# STM32_CANbus_V01.net
KiCad netlist of a schematic drawn in EAGLE
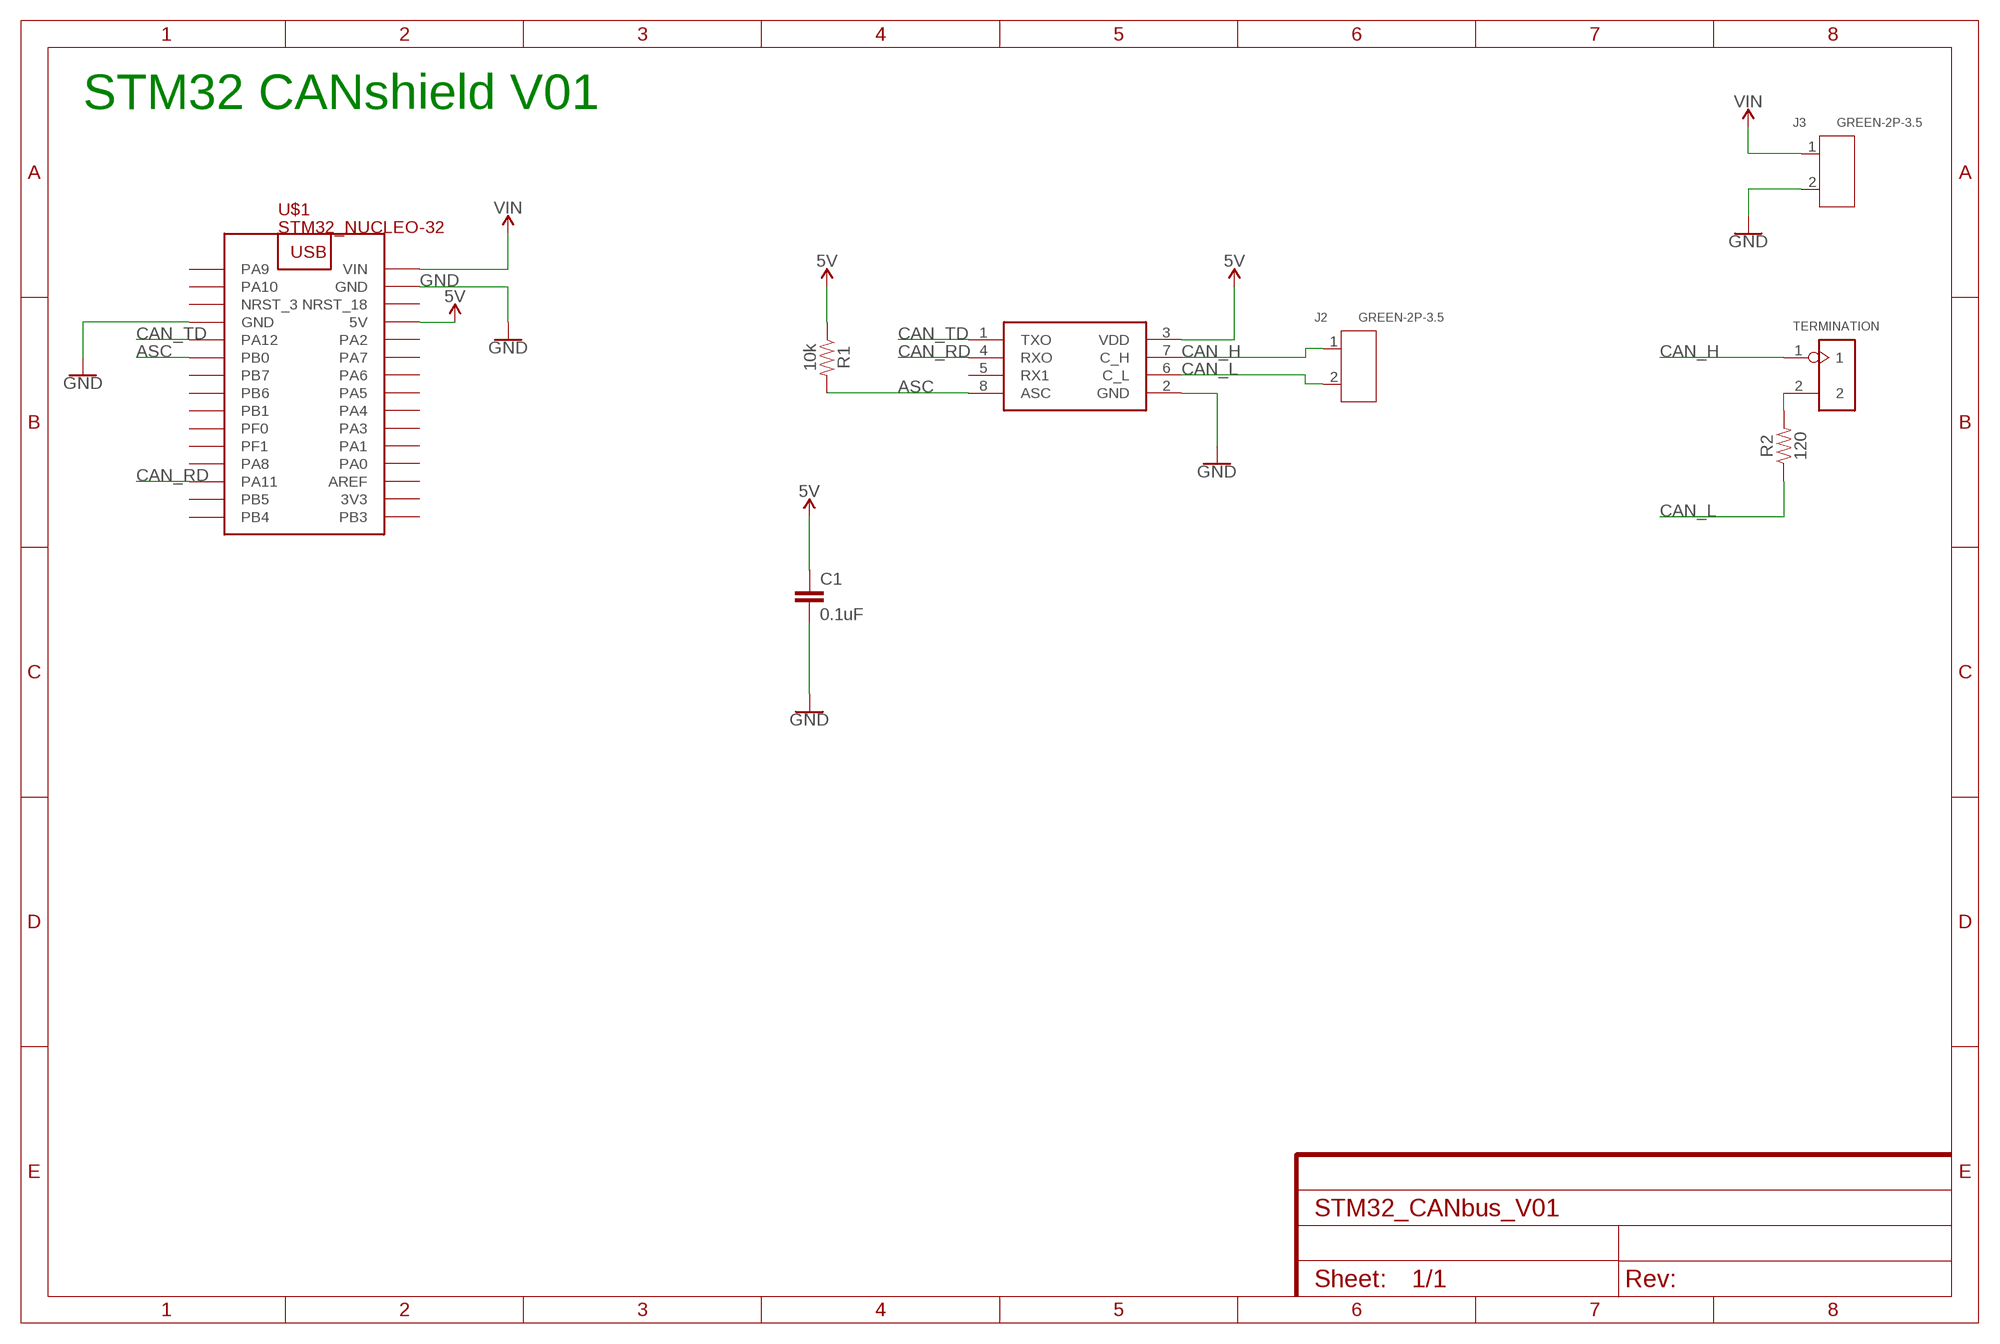
[diagram p0: schematic, sheet 1]

(export (version "E")
  (design (tool "Eeschema 10.0.6"))
  (components
    (comp (ref "C")
      (value "L9616")
      (footprint "eagle-import:SO8")
      (fields (field (name "MF") "STMicroelectronics"))
      (libsource (lib "eagle-import") (part "L9616"))
    )
    (comp (ref "C1")
      (value "0.1uF")
      (footprint "eagle-import:0805")
      (libsource (lib "eagle-import") (part "1.0UF-0805-25V-10%"))
    )
    (comp (ref "J2")
      (value "GREEN-2P-3.5")
      (footprint "eagle-import:H2-3.5-7.0X7.0MM")
      (libsource (lib "eagle-import") (part "SCREW-TERMINAL-GREEN(2P-3.5)"))
    )
    (comp (ref "J3")
      (value "GREEN-2P-3.5")
      (footprint "eagle-import:H2-3.5-7.0X7.0MM")
      (libsource (lib "eagle-import") (part "SCREW-TERMINAL-GREEN(2P-3.5)"))
    )
    (comp (ref "R1")
      (value "10k")
      (footprint "eagle-import:0805")
      (libsource (lib "eagle-import") (part "RESISTOR0805"))
    )
    (comp (ref "R2")
      (value "120")
      (footprint "eagle-import:1206")
      (libsource (lib "eagle-import") (part "RESISTOR1206"))
    )
    (comp (ref "TERMINATION")
      (value "DIP-BLACK-JUMPER")
      (footprint "eagle-import:H2-2.54")
      (libsource (lib "eagle-import") (part "DIP-BLACK-JUMPER"))
    )
    (comp (ref "U$1")
      (value "STM32_NUCLEO-32")
      (footprint "eagle-import:STM32_NUCLEO-32")
      (libsource (lib "eagle-import") (part "STM32_NUCLEO-32"))
    )
  )
  (nets
    (net (code "1") (name "/3V3") (class "Default")
      (node (ref "U$1") (pin "3V3") (pinfunction "3V3_3V3") (pintype "power_in"))
    )
    (net (code "2") (name "/ASC") (class "Default")
      (node (ref "C") (pin "8") (pinfunction "ASC_8") (pintype "bidirectional"))
      (node (ref "R1") (pin "2") (pinfunction "2_2") (pintype "passive"))
      (node (ref "U$1") (pin "PB0") (pinfunction "PB0_PB0") (pintype "bidirectional"))
    )
    (net (code "3") (name "/CAN_H") (class "Default")
      (node (ref "C") (pin "7") (pinfunction "C_H_7") (pintype "bidirectional"))
      (node (ref "J2") (pin "1") (pinfunction "1_1") (pintype "bidirectional"))
      (node (ref "TERMINATION") (pin "1") (pinfunction "1_1") (pintype "bidirectional"))
    )
    (net (code "4") (name "/CAN_L") (class "Default")
      (node (ref "C") (pin "6") (pinfunction "C_L_6") (pintype "bidirectional"))
      (node (ref "J2") (pin "2") (pinfunction "2_2") (pintype "bidirectional"))
      (node (ref "R2") (pin "1") (pinfunction "1_1") (pintype "passive"))
    )
    (net (code "5") (name "/CAN_RD") (class "Default")
      (node (ref "C") (pin "4") (pinfunction "RXO_4") (pintype "bidirectional"))
      (node (ref "U$1") (pin "PA11") (pinfunction "PA11_PA11") (pintype "bidirectional"))
    )
    (net (code "6") (name "/CAN_TD") (class "Default")
      (node (ref "C") (pin "1") (pinfunction "TXO_1") (pintype "bidirectional"))
      (node (ref "U$1") (pin "PA12") (pinfunction "PA12_PA12") (pintype "bidirectional"))
    )
    (net (code "7") (name "5V") (class "Default")
      (node (ref "C") (pin "3") (pinfunction "VDD_3") (pintype "bidirectional"))
      (node (ref "C1") (pin "1") (pinfunction "1_1") (pintype "passive"))
      (node (ref "R1") (pin "1") (pinfunction "1_1") (pintype "passive"))
      (node (ref "U$1") (pin "5V") (pinfunction "5V_5V") (pintype "power_in"))
    )
    (net (code "8") (name "GND") (class "Default")
      (node (ref "C") (pin "2") (pinfunction "GND_2") (pintype "bidirectional"))
      (node (ref "C1") (pin "2") (pinfunction "2_2") (pintype "passive"))
      (node (ref "J3") (pin "2") (pinfunction "2_2") (pintype "bidirectional"))
      (node (ref "U$1") (pin "GND@17") (pinfunction "GND_GND@17") (pintype "power_in"))
      (node (ref "U$1") (pin "GND@4") (pinfunction "GND_GND@4") (pintype "power_in"))
    )
    (net (code "9") (name "Net-(R2-Pad2)") (class "Default")
      (node (ref "R2") (pin "2") (pinfunction "2_2") (pintype "passive"))
      (node (ref "TERMINATION") (pin "2") (pinfunction "2_2") (pintype "bidirectional"))
    )
    (net (code "10") (name "VIN") (class "Default")
      (node (ref "J3") (pin "1") (pinfunction "1_1") (pintype "bidirectional"))
      (node (ref "U$1") (pin "VIN") (pinfunction "VIN_VIN") (pintype "power_in"))
    )
    (net (code "11") (name "unconnected-(C-RX1-Pad5)") (class "Default")
      (node (ref "C") (pin "5") (pinfunction "RX1_5") (pintype "bidirectional"))
    )
    (net (code "12") (name "unconnected-(U$1-PadAREF)") (class "Default")
      (node (ref "U$1") (pin "AREF") (pinfunction "AREF_AREF") (pintype "bidirectional"))
    )
    (net (code "13") (name "unconnected-(U$1-PadNRST_3)") (class "Default")
      (node (ref "U$1") (pin "NRST_3") (pinfunction "NRST_3_NRST_3") (pintype "bidirectional"))
    )
    (net (code "14") (name "unconnected-(U$1-PadNRST_18)") (class "Default")
      (node (ref "U$1") (pin "NRST_18") (pinfunction "NRST_18_NRST_18") (pintype "bidirectional"))
    )
    (net (code "15") (name "unconnected-(U$1-PadPA0)") (class "Default")
      (node (ref "U$1") (pin "PA0") (pinfunction "PA0_PA0") (pintype "bidirectional"))
    )
    (net (code "16") (name "unconnected-(U$1-PadPA1)") (class "Default")
      (node (ref "U$1") (pin "PA1") (pinfunction "PA1_PA1") (pintype "bidirectional"))
    )
    (net (code "17") (name "unconnected-(U$1-PadPA2)") (class "Default")
      (node (ref "U$1") (pin "PA2") (pinfunction "PA2_PA2") (pintype "bidirectional"))
    )
    (net (code "18") (name "unconnected-(U$1-PadPA3)") (class "Default")
      (node (ref "U$1") (pin "PA3") (pinfunction "PA3_PA3") (pintype "bidirectional"))
    )
    (net (code "19") (name "unconnected-(U$1-PadPA4)") (class "Default")
      (node (ref "U$1") (pin "PA4") (pinfunction "PA4_PA4") (pintype "bidirectional"))
    )
    (net (code "20") (name "unconnected-(U$1-PadPA5)") (class "Default")
      (node (ref "U$1") (pin "PA5") (pinfunction "PA5_PA5") (pintype "bidirectional"))
    )
    (net (code "21") (name "unconnected-(U$1-PadPA6)") (class "Default")
      (node (ref "U$1") (pin "PA6") (pinfunction "PA6_PA6") (pintype "bidirectional"))
    )
    (net (code "22") (name "unconnected-(U$1-PadPA7)") (class "Default")
      (node (ref "U$1") (pin "PA7") (pinfunction "PA7_PA7") (pintype "bidirectional"))
    )
    (net (code "23") (name "unconnected-(U$1-PadPA8)") (class "Default")
      (node (ref "U$1") (pin "PA8") (pinfunction "PA8_PA8") (pintype "bidirectional"))
    )
    (net (code "24") (name "unconnected-(U$1-PadPA9)") (class "Default")
      (node (ref "U$1") (pin "PA9") (pinfunction "PA9_PA9") (pintype "bidirectional"))
    )
    (net (code "25") (name "unconnected-(U$1-PadPA10)") (class "Default")
      (node (ref "U$1") (pin "PA10") (pinfunction "PA10_PA10") (pintype "bidirectional"))
    )
    (net (code "26") (name "unconnected-(U$1-PadPB1)") (class "Default")
      (node (ref "U$1") (pin "PB1") (pinfunction "PB1_PB1") (pintype "bidirectional"))
    )
    (net (code "27") (name "unconnected-(U$1-PadPB3)") (class "Default")
      (node (ref "U$1") (pin "PB3") (pinfunction "PB3_PB3") (pintype "bidirectional"))
    )
    (net (code "28") (name "unconnected-(U$1-PadPB4)") (class "Default")
      (node (ref "U$1") (pin "PB4") (pinfunction "PB4_PB4") (pintype "bidirectional"))
    )
    (net (code "29") (name "unconnected-(U$1-PadPB5)") (class "Default")
      (node (ref "U$1") (pin "PB5") (pinfunction "PB5_PB5") (pintype "bidirectional"))
    )
    (net (code "30") (name "unconnected-(U$1-PadPB6)") (class "Default")
      (node (ref "U$1") (pin "PB6") (pinfunction "PB6_PB6") (pintype "bidirectional"))
    )
    (net (code "31") (name "unconnected-(U$1-PadPB7)") (class "Default")
      (node (ref "U$1") (pin "PB7") (pinfunction "PB7_PB7") (pintype "bidirectional"))
    )
    (net (code "32") (name "unconnected-(U$1-PadPF0)") (class "Default")
      (node (ref "U$1") (pin "PF0") (pinfunction "PF0_PF0") (pintype "bidirectional"))
    )
    (net (code "33") (name "unconnected-(U$1-PadPF1)") (class "Default")
      (node (ref "U$1") (pin "PF1") (pinfunction "PF1_PF1") (pintype "bidirectional"))
    )
  )
)
